# CON_RS485_PWR_RJ45X2.net
KiCad netlist of a schematic drawn in Altium Designer
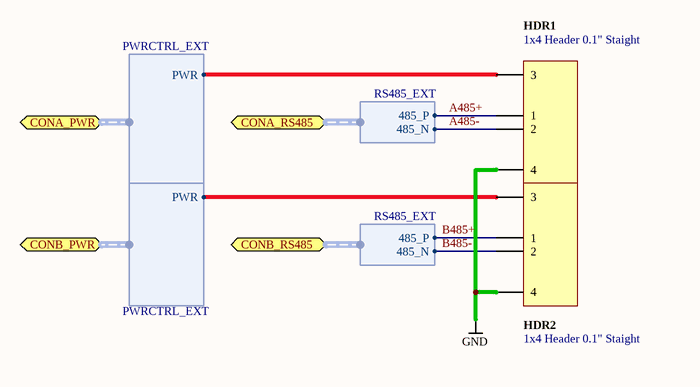
[diagram p0: CON_RS485_PWR_RJ45X2.SchDoc]

(export (version "E")
  (design (tool "Eeschema 10.0.6"))
  (components
    (comp (ref "HDR1")
      (value "1x4 Header 0.1\" Staight")
      (footprint "HDR1X4")
      (description "Header, 1x4, 0.1\", Straight, 15mm High")
      (libsource (lib "AltiumDesignLibrary") (part "CON-HDR-1X8-STR"))
    )
    (comp (ref "HDR2")
      (value "1x4 Header 0.1\" Staight")
      (footprint "HDR1X4")
      (description "Header, 1x4, 0.1\", Straight, 15mm High")
      (libsource (lib "AltiumDesignLibrary") (part "CON-HDR-1X8-STR"))
    )
  )
  (nets
    (net (code "3") (name "/A485+") (class "Default")
      (node (ref "HDR1") (pin "1") (pinfunction "1_1") (pintype "passive"))
    )
    (net (code "4") (name "/A485-") (class "Default")
      (node (ref "HDR1") (pin "2") (pinfunction "2_2") (pintype "passive"))
    )
    (net (code "5") (name "/B485+") (class "Default")
      (node (ref "HDR2") (pin "1") (pinfunction "1_1") (pintype "passive"))
    )
    (net (code "6") (name "/B485-") (class "Default")
      (node (ref "HDR2") (pin "2") (pinfunction "2_2") (pintype "passive"))
    )
    (net (code "9") (name "GND") (class "Default")
      (node (ref "HDR1") (pin "4") (pinfunction "4_4") (pintype "passive"))
      (node (ref "HDR2") (pin "4") (pinfunction "4_4") (pintype "passive"))
    )
    (net (code "10") (name "unconnected-(HDR1-Pad3)") (class "Default")
      (node (ref "HDR1") (pin "3") (pinfunction "3_3") (pintype "passive"))
    )
    (net (code "11") (name "unconnected-(HDR2-Pad3)") (class "Default")
      (node (ref "HDR2") (pin "3") (pinfunction "3_3") (pintype "passive"))
    )
  )
)
